# rad_detector_v500_HV_PSU.net
KiCad netlist of a schematic drawn in Altium Designer
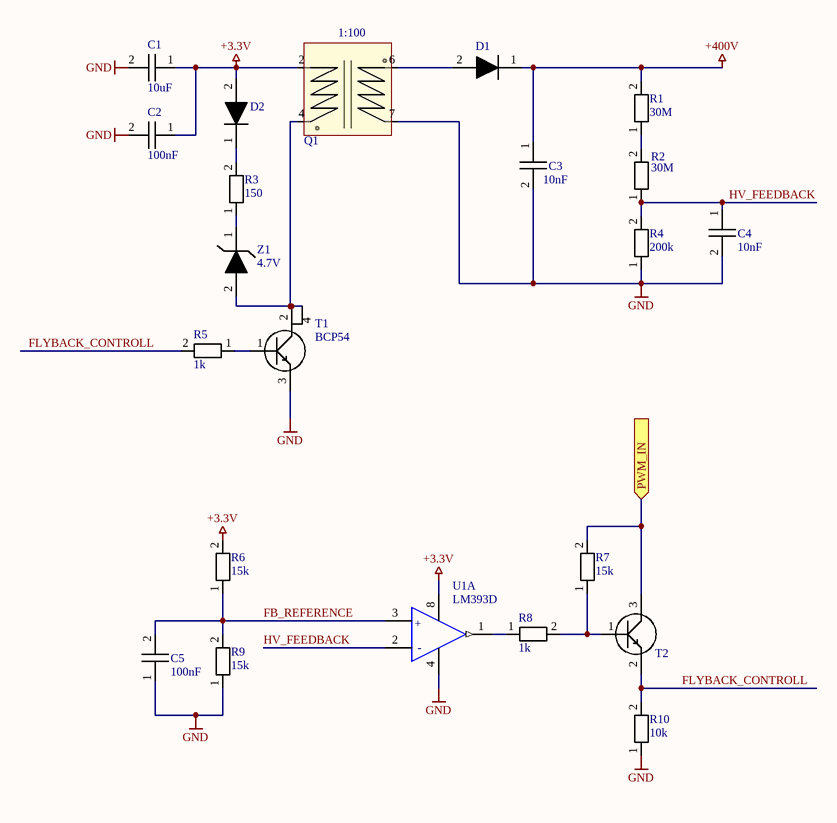
[diagram p0: rad_detector_v500_HV_PSU.SchDoc]

(export (version "E")
  (design (tool "Eeschema 10.0.6"))
  (components
    (comp (ref "C1") (value "10uF") (footprint "1210_C") (libsource (lib "Schlib1") (part "CAPACITOR")))
    (comp (ref "C2") (value "100nF") (footprint "0805_C") (libsource (lib "Schlib1") (part "CAPACITOR")))
    (comp (ref "C3")
      (value "10nF")
      (footprint "CAPACITOR_300MIL")
      (libsource (lib "Schlib1") (part "CAPACITOR"))
    )
    (comp (ref "C4") (value "10nF") (footprint "0805_C") (libsource (lib "Schlib1") (part "CAPACITOR")))
    (comp (ref "C5") (value "100nF") (footprint "0805_C") (libsource (lib "Schlib1") (part "CAPACITOR")))
    (comp (ref "D1") (value "DIODE") (footprint "DIODE_400MIL") (libsource (lib "Schlib1") (part "DIODE")))
    (comp (ref "D2") (value "DIODE") (footprint "SMD_DIODE_SOD80") (libsource (lib "Schlib1") (part "DIODE")))
    (comp (ref "Q1")
      (value "DARFON_CCFL_TRANSFORMER")
      (footprint "DARFON_CCFL_TRANSFORMER")
      (libsource (lib "Schlib1") (part "DARFON_CCFL_TRANSFORMER"))
    )
    (comp (ref "R1") (value "30M") (footprint "0805") (libsource (lib "Schlib1") (part "RESISTOR")))
    (comp (ref "R2") (value "30M") (footprint "0805") (libsource (lib "Schlib1") (part "RESISTOR")))
    (comp (ref "R3") (value "150") (footprint "0805") (libsource (lib "Schlib1") (part "RESISTOR")))
    (comp (ref "R4") (value "200k") (footprint "0805") (libsource (lib "Schlib1") (part "RESISTOR")))
    (comp (ref "R5") (value "1k") (footprint "0805") (libsource (lib "Schlib1") (part "RESISTOR")))
    (comp (ref "R6") (value "15k") (footprint "0805") (libsource (lib "Schlib1") (part "RESISTOR")))
    (comp (ref "R7") (value "15k") (footprint "0805") (libsource (lib "Schlib1") (part "RESISTOR")))
    (comp (ref "R8") (value "1k") (footprint "0805") (libsource (lib "Schlib1") (part "RESISTOR")))
    (comp (ref "R9") (value "15k") (footprint "0805") (libsource (lib "Schlib1") (part "RESISTOR")))
    (comp (ref "R10") (value "10k") (footprint "0805") (libsource (lib "Schlib1") (part "RESISTOR")))
    (comp (ref "T1") (value "BCP54") (footprint "SOT233-1") (libsource (lib "Schlib1") (part "BCP54")))
    (comp (ref "T2") (value "BC848*") (footprint "SOT23") (libsource (lib "Schlib1") (part "TRANSISTOR_NPN")))
    (comp (ref "U1")
      (value "LM393D")
      (footprint "SO-8")
      (description "IC VOLT COMPARATOR DUAL LP 8SOIC")
      (fields
        (field (name "OCTOPART") "https://octopart.com/lm393d-stmicroelectronics-25832")
        (field (name "MANUFACTURER") "STMicroelectronics")
      )
      (libsource (lib "ic_modules") (part "LM393D"))
    )
    (comp (ref "Z1")
      (value "4.7V")
      (footprint "SMD_DIODE_SOD80")
      (libsource (lib "Schlib1") (part "DIODE_ZENER"))
    )
  )
  (nets
    (net (code "1") (name "+3.3V") (class "Default")
      (node (ref "C1") (pin "1") (pinfunction "1_1") (pintype "passive"))
      (node (ref "C2") (pin "1") (pinfunction "1_1") (pintype "passive"))
      (node (ref "D2") (pin "2") (pinfunction "2_2") (pintype "passive"))
      (node (ref "Q1") (pin "2") (pinfunction "2_2") (pintype "passive"))
      (node (ref "R6") (pin "2") (pinfunction "1_2") (pintype "passive"))
      (node (ref "U1") (pin "8") (pinfunction "Vcc+_8") (pintype "power_in"))
    )
    (net (code "2") (name "+400V") (class "Default")
      (node (ref "C3") (pin "1") (pinfunction "1_1") (pintype "passive"))
      (node (ref "D1") (pin "1") (pinfunction "1_1") (pintype "passive"))
      (node (ref "R1") (pin "2") (pinfunction "1_2") (pintype "passive"))
    )
    (net (code "3") (name "/FB_REFERENCE") (class "Default")
      (node (ref "C5") (pin "2") (pinfunction "2_2") (pintype "passive"))
      (node (ref "R6") (pin "1") (pinfunction "0_1") (pintype "passive"))
      (node (ref "R9") (pin "2") (pinfunction "1_2") (pintype "passive"))
      (node (ref "U1") (pin "3") (pinfunction "In1+_3") (pintype "tri_state"))
    )
    (net (code "4") (name "/FLYBACK_CONTROLL") (class "Default")
      (node (ref "R10") (pin "2") (pinfunction "1_2") (pintype "passive"))
      (node (ref "R5") (pin "2") (pinfunction "1_2") (pintype "passive"))
      (node (ref "T2") (pin "2") (pinfunction "2_2") (pintype "passive"))
    )
    (net (code "5") (name "/HV_FEEDBACK") (class "Default")
      (node (ref "C4") (pin "1") (pinfunction "1_1") (pintype "passive"))
      (node (ref "R2") (pin "1") (pinfunction "0_1") (pintype "passive"))
      (node (ref "R4") (pin "2") (pinfunction "1_2") (pintype "passive"))
      (node (ref "U1") (pin "2") (pinfunction "In1-_2") (pintype "tri_state"))
    )
    (net (code "6") (name "/PWM_IN") (class "Default")
      (node (ref "R7") (pin "2") (pinfunction "1_2") (pintype "passive"))
      (node (ref "T2") (pin "3") (pinfunction "3_3") (pintype "passive"))
    )
    (net (code "7") (name "GND") (class "Default")
      (node (ref "C1") (pin "2") (pinfunction "2_2") (pintype "passive"))
      (node (ref "C2") (pin "2") (pinfunction "2_2") (pintype "passive"))
      (node (ref "C3") (pin "2") (pinfunction "2_2") (pintype "passive"))
      (node (ref "C4") (pin "2") (pinfunction "2_2") (pintype "passive"))
      (node (ref "C5") (pin "1") (pinfunction "1_1") (pintype "passive"))
      (node (ref "Q1") (pin "7") (pinfunction "7_7") (pintype "passive"))
      (node (ref "R10") (pin "1") (pinfunction "0_1") (pintype "passive"))
      (node (ref "R4") (pin "1") (pinfunction "0_1") (pintype "passive"))
      (node (ref "R9") (pin "1") (pinfunction "0_1") (pintype "passive"))
      (node (ref "T1") (pin "3") (pinfunction "3_3") (pintype "passive"))
      (node (ref "U1") (pin "4") (pinfunction "Vcc-_4") (pintype "power_in"))
    )
    (net (code "8") (name "Net-(D1-Pad2)") (class "Default")
      (node (ref "D1") (pin "2") (pinfunction "2_2") (pintype "passive"))
      (node (ref "Q1") (pin "6") (pinfunction "6_6") (pintype "passive"))
    )
    (net (code "9") (name "Net-(Q1-Pad4)") (class "Default")
      (node (ref "Q1") (pin "4") (pinfunction "4_4") (pintype "passive"))
      (node (ref "T1") (pin "2") (pinfunction "2_2") (pintype "passive"))
      (node (ref "T1") (pin "4") (pinfunction "4_4") (pintype "passive"))
      (node (ref "Z1") (pin "2") (pinfunction "2_2") (pintype "passive"))
    )
    (net (code "10") (name "Net-(R1-0)") (class "Default")
      (node (ref "R1") (pin "1") (pinfunction "0_1") (pintype "passive"))
      (node (ref "R2") (pin "2") (pinfunction "1_2") (pintype "passive"))
    )
    (net (code "11") (name "Net-(R3-0)") (class "Default")
      (node (ref "R3") (pin "1") (pinfunction "0_1") (pintype "passive"))
      (node (ref "Z1") (pin "1") (pinfunction "1_1") (pintype "passive"))
    )
    (net (code "12") (name "Net-(R3-1)") (class "Default")
      (node (ref "D2") (pin "1") (pinfunction "1_1") (pintype "passive"))
      (node (ref "R3") (pin "2") (pinfunction "1_2") (pintype "passive"))
    )
    (net (code "13") (name "Net-(R5-0)") (class "Default")
      (node (ref "R5") (pin "1") (pinfunction "0_1") (pintype "passive"))
      (node (ref "T1") (pin "1") (pinfunction "1_1") (pintype "passive"))
    )
    (net (code "14") (name "Net-(R7-0)") (class "Default")
      (node (ref "R7") (pin "1") (pinfunction "0_1") (pintype "passive"))
      (node (ref "R8") (pin "2") (pinfunction "1_2") (pintype "passive"))
      (node (ref "T2") (pin "1") (pinfunction "1_1") (pintype "passive"))
    )
    (net (code "15") (name "Net-(R8-0)") (class "Default")
      (node (ref "R8") (pin "1") (pinfunction "0_1") (pintype "passive"))
      (node (ref "U1") (pin "1") (pinfunction "Out1_1") (pintype "output"))
    )
  )
)
